# BT_module.net
KiCad netlist of a schematic drawn in EAGLE
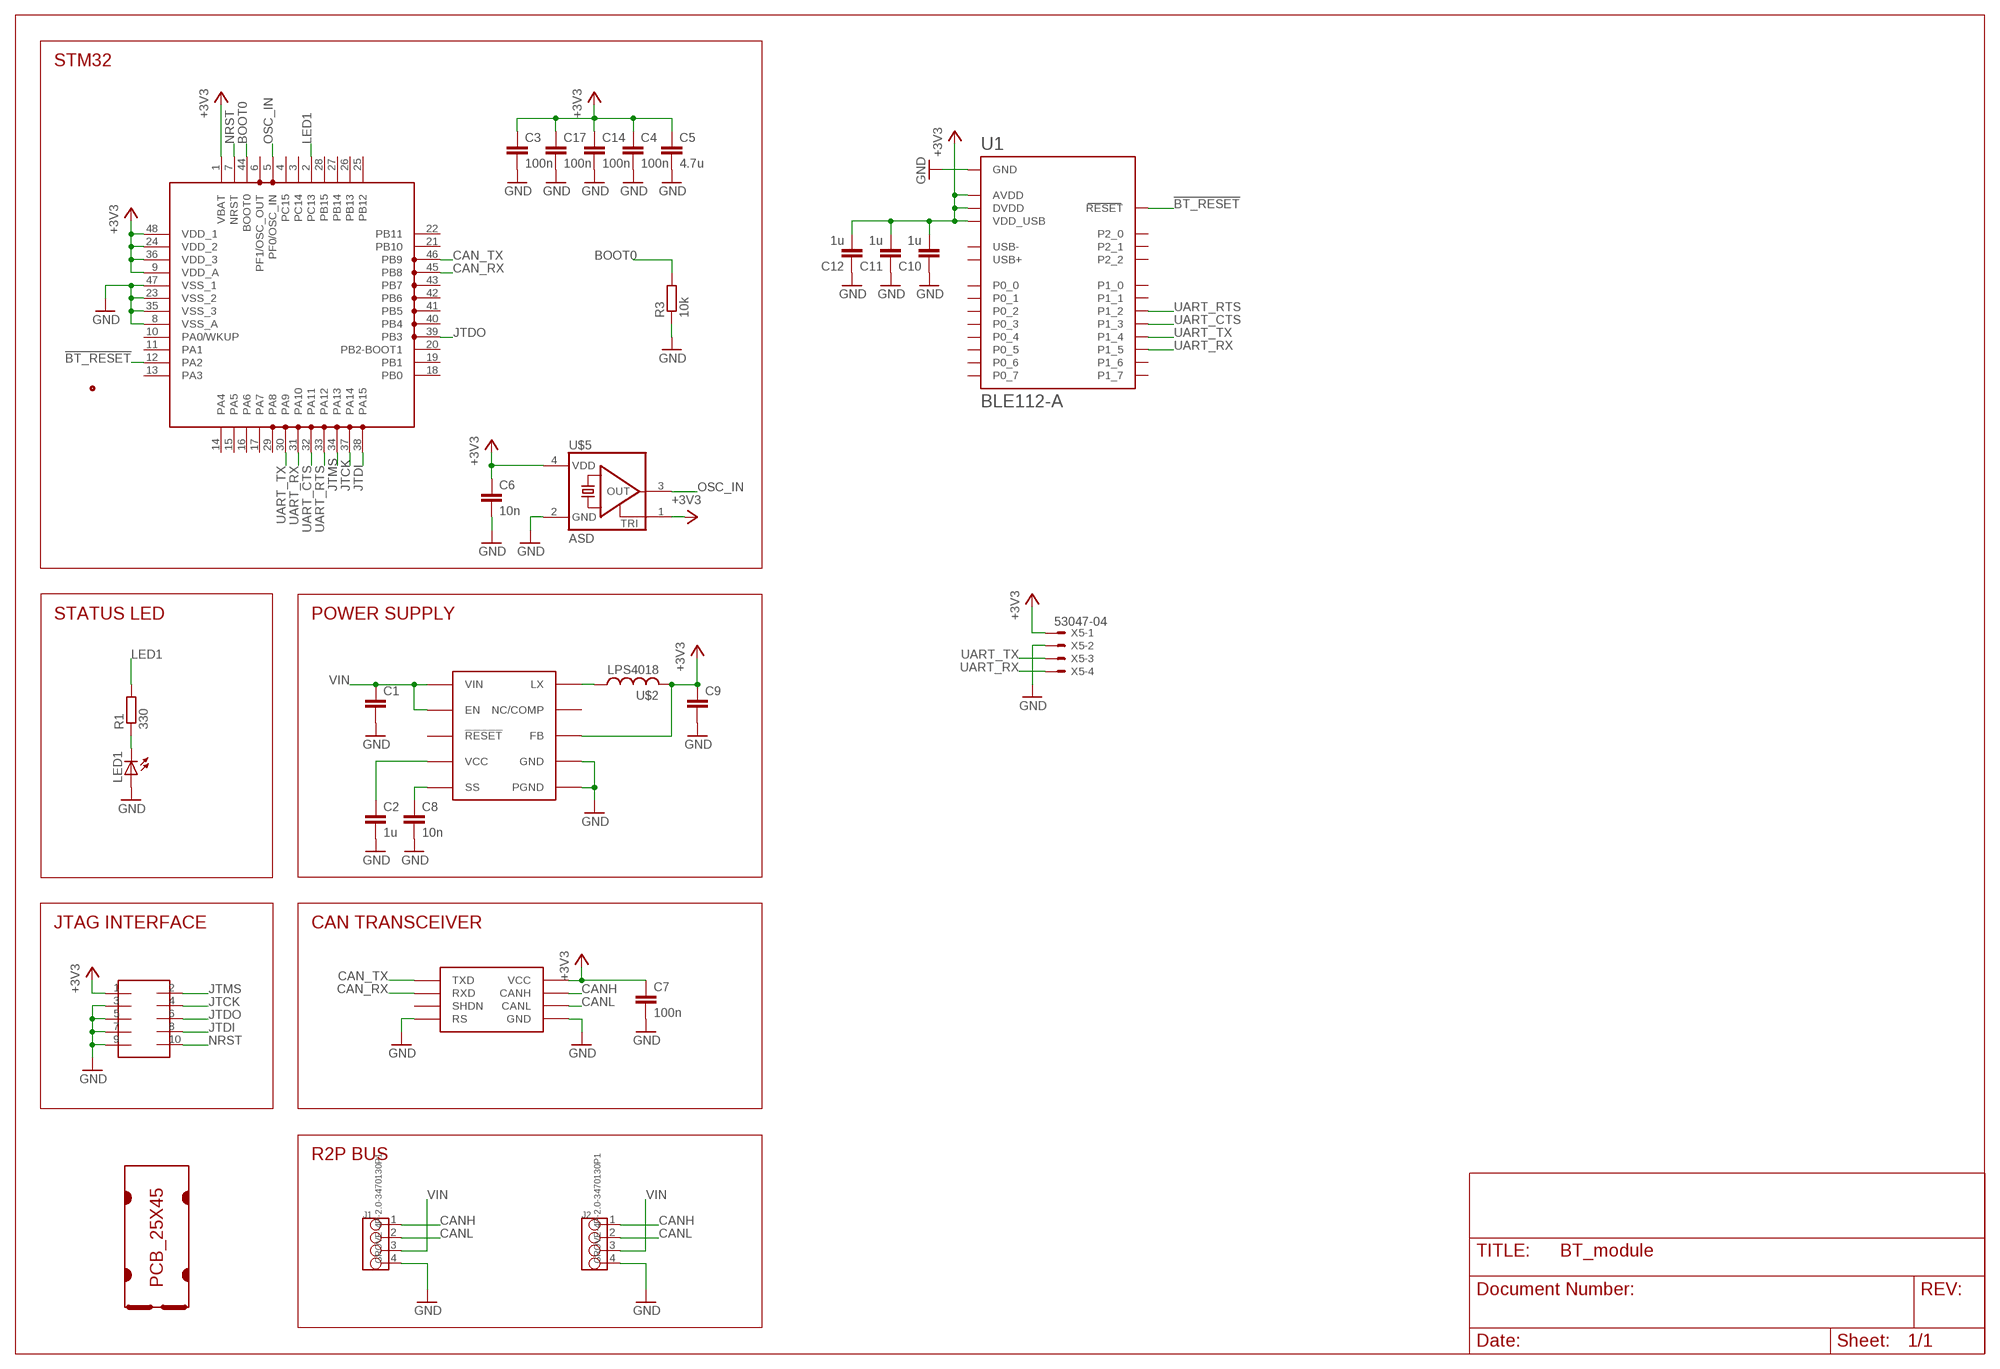
[diagram p0: schematic, sheet 1]

(export (version "E")
  (design (tool "Eeschema 10.0.6"))
  (components
    (comp (ref "C1")
      (value "C-EUC1206")
      (footprint "eagle-import:C1206")
      (libsource (lib "eagle-import") (part "C-EUC1206"))
    )
    (comp (ref "C2")
      (value "1u")
      (footprint "eagle-import:C0603")
      (libsource (lib "eagle-import") (part "C-EUC0603"))
    )
    (comp (ref "C3")
      (value "100n")
      (footprint "eagle-import:C0603")
      (libsource (lib "eagle-import") (part "C-EUC0603"))
    )
    (comp (ref "C4")
      (value "100n")
      (footprint "eagle-import:C0603")
      (libsource (lib "eagle-import") (part "C-EUC0603"))
    )
    (comp (ref "C5")
      (value "4.7u")
      (footprint "eagle-import:C0805")
      (libsource (lib "eagle-import") (part "C-EUC0805"))
    )
    (comp (ref "C6")
      (value "10n")
      (footprint "eagle-import:C0603")
      (libsource (lib "eagle-import") (part "C-EUC0603"))
    )
    (comp (ref "C7")
      (value "100n")
      (footprint "eagle-import:C0603")
      (libsource (lib "eagle-import") (part "C-EUC0603"))
    )
    (comp (ref "C8")
      (value "10n")
      (footprint "eagle-import:C0603")
      (libsource (lib "eagle-import") (part "C-EUC0603"))
    )
    (comp (ref "C9")
      (value "C-EUC0805")
      (footprint "eagle-import:C0805")
      (libsource (lib "eagle-import") (part "C-EUC0805"))
    )
    (comp (ref "C10")
      (value "1u")
      (footprint "eagle-import:C0603")
      (libsource (lib "eagle-import") (part "C-EUC0603"))
    )
    (comp (ref "C11")
      (value "1u")
      (footprint "eagle-import:C0603")
      (libsource (lib "eagle-import") (part "C-EUC0603"))
    )
    (comp (ref "C12")
      (value "1u")
      (footprint "eagle-import:C0603")
      (libsource (lib "eagle-import") (part "C-EUC0603"))
    )
    (comp (ref "C14")
      (value "100n")
      (footprint "eagle-import:C0603")
      (libsource (lib "eagle-import") (part "C-EUC0603"))
    )
    (comp (ref "C17")
      (value "100n")
      (footprint "eagle-import:C0603")
      (libsource (lib "eagle-import") (part "C-EUC0603"))
    )
    (comp (ref "J1")
      (value "GROVE-4P-2.0-3470130P1")
      (footprint "eagle-import:4P-2.0")
      (libsource (lib "eagle-import") (part "GROVE-4P-2.0-3470130P1"))
    )
    (comp (ref "J2")
      (value "GROVE-4P-2.0-3470130P1")
      (footprint "eagle-import:4P-2.0")
      (libsource (lib "eagle-import") (part "GROVE-4P-2.0-3470130P1"))
    )
    (comp (ref "LED1")
      (value "LEDCHIPLED_0805")
      (footprint "eagle-import:CHIPLED_0805")
      (libsource (lib "eagle-import") (part "LEDCHIPLED_0805"))
    )
    (comp (ref "R1")
      (value "330")
      (footprint "eagle-import:R0603")
      (libsource (lib "eagle-import") (part "R-EU_R0603"))
    )
    (comp (ref "R3")
      (value "10k")
      (footprint "eagle-import:R0603")
      (libsource (lib "eagle-import") (part "R-EU_R0603"))
    )
    (comp (ref "SOT1")
      (value "MAX3051EKA")
      (footprint "eagle-import:SOT23-8L")
      (libsource (lib "eagle-import") (part "MAX3051EKA"))
    )
    (comp (ref "U$1")
      (value "PCB_25X45")
      (footprint "eagle-import:25X45")
      (libsource (lib "eagle-import") (part "PCB_25X45"))
    )
    (comp (ref "U$2")
      (value "LPS4018")
      (footprint "eagle-import:LPS4018")
      (libsource (lib "eagle-import") (part "LPS4018"))
    )
    (comp (ref "U$3")
      (value "MAX17501")
      (footprint "eagle-import:TDFN-10")
      (libsource (lib "eagle-import") (part "MAX17501"))
    )
    (comp (ref "U$4")
      (value "FTSH-105TH")
      (footprint "eagle-import:FTSH-105-TH")
      (libsource (lib "eagle-import") (part "FTSH-105TH"))
    )
    (comp (ref "U$5")
      (value "ASD")
      (footprint "eagle-import:2.5X2")
      (libsource (lib "eagle-import") (part "ASD"))
    )
    (comp (ref "U$6")
      (value "STM32F303C")
      (footprint "eagle-import:LQFP48")
      (libsource (lib "eagle-import") (part "STM32F303C"))
    )
    (comp (ref "U1")
      (value "BLE112-A")
      (footprint "eagle-import:BLE112-A")
      (libsource (lib "eagle-import") (part "BLE112-A"))
    )
    (comp (ref "X5")
      (value "53047-04")
      (footprint "eagle-import:53047-04")
      (fields (field (name "MF") "WALDOM/MOLEX") (field (name "MPN") "53047-0410"))
      (libsource (lib "eagle-import") (part "53?-04047"))
    )
  )
  (nets
    (net (code "1") (name "+3V3") (class "Default")
      (node (ref "C10") (pin "2") (pinfunction "2_2") (pintype "passive"))
      (node (ref "C11") (pin "2") (pinfunction "2_2") (pintype "passive"))
      (node (ref "C12") (pin "2") (pinfunction "2_2") (pintype "passive"))
      (node (ref "C14") (pin "1") (pinfunction "1_1") (pintype "passive"))
      (node (ref "C17") (pin "1") (pinfunction "1_1") (pintype "passive"))
      (node (ref "C3") (pin "1") (pinfunction "1_1") (pintype "passive"))
      (node (ref "C4") (pin "1") (pinfunction "1_1") (pintype "passive"))
      (node (ref "C5") (pin "1") (pinfunction "1_1") (pintype "passive"))
      (node (ref "C6") (pin "1") (pinfunction "1_1") (pintype "passive"))
      (node (ref "C7") (pin "1") (pinfunction "1_1") (pintype "passive"))
      (node (ref "C9") (pin "1") (pinfunction "1_1") (pintype "passive"))
      (node (ref "SOT1") (pin "3") (pinfunction "VCC_3") (pintype "bidirectional"))
      (node (ref "U$2") (pin "P$2") (pinfunction "2_P$2") (pintype "passive"))
      (node (ref "U$3") (pin "P$5") (pinfunction "FB_P$5") (pintype "bidirectional"))
      (node (ref "U$4") (pin "1") (pinfunction "P$1_1") (pintype "bidirectional"))
      (node (ref "U$5") (pin "1") (pinfunction "TRI_1") (pintype "input"))
      (node (ref "U$5") (pin "4") (pinfunction "VDD_4") (pintype "power_in"))
      (node (ref "U$6") (pin "1") (pinfunction "VBAT_1") (pintype "bidirectional"))
      (node (ref "U$6") (pin "24") (pinfunction "VDD_2_24") (pintype "bidirectional"))
      (node (ref "U$6") (pin "36") (pinfunction "VDD_3_36") (pintype "bidirectional"))
      (node (ref "U$6") (pin "48") (pinfunction "VDD_1_48") (pintype "bidirectional"))
      (node (ref "U$6") (pin "9") (pinfunction "VDD_A_9") (pintype "bidirectional"))
      (node (ref "U1") (pin "AVDD") (pinfunction "AVDD_AVDD") (pintype "power_in"))
      (node (ref "U1") (pin "AVDD@2") (pinfunction "AVDD_AVDD@2") (pintype "power_in"))
      (node (ref "U1") (pin "DVDD") (pinfunction "DVDD_DVDD") (pintype "power_in"))
      (node (ref "U1") (pin "VDD_USB") (pinfunction "VDD_USB_VDD_USB") (pintype "power_in"))
      (node (ref "X5") (pin "1") (pinfunction "S_1") (pintype "passive"))
    )
    (net (code "2") (name "/BOOT0") (class "Default")
      (node (ref "R3") (pin "2") (pinfunction "2_2") (pintype "passive"))
      (node (ref "U$6") (pin "44") (pinfunction "BOOT0_44") (pintype "bidirectional"))
    )
    (net (code "3") (name "/CANH") (class "Default")
      (node (ref "J1") (pin "1") (pinfunction "1_1") (pintype "bidirectional"))
      (node (ref "J2") (pin "1") (pinfunction "1_1") (pintype "bidirectional"))
      (node (ref "SOT1") (pin "7") (pinfunction "CANH_7") (pintype "bidirectional"))
    )
    (net (code "4") (name "/CANL") (class "Default")
      (node (ref "J1") (pin "2") (pinfunction "2_2") (pintype "bidirectional"))
      (node (ref "J2") (pin "2") (pinfunction "2_2") (pintype "bidirectional"))
      (node (ref "SOT1") (pin "6") (pinfunction "CANL_6") (pintype "bidirectional"))
    )
    (net (code "5") (name "/CAN_RX") (class "Default")
      (node (ref "SOT1") (pin "4") (pinfunction "RXD_4") (pintype "bidirectional"))
      (node (ref "U$6") (pin "45") (pinfunction "PB8_45") (pintype "bidirectional"))
    )
    (net (code "6") (name "/CAN_TX") (class "Default")
      (node (ref "SOT1") (pin "1") (pinfunction "TXD_1") (pintype "bidirectional"))
      (node (ref "U$6") (pin "46") (pinfunction "PB9_46") (pintype "bidirectional"))
    )
    (net (code "7") (name "/JTCK") (class "Default")
      (node (ref "U$4") (pin "4") (pinfunction "P$4_4") (pintype "bidirectional"))
      (node (ref "U$6") (pin "37") (pinfunction "PA14_37") (pintype "bidirectional"))
    )
    (net (code "8") (name "/JTDI") (class "Default")
      (node (ref "U$4") (pin "8") (pinfunction "P$8_8") (pintype "bidirectional"))
      (node (ref "U$6") (pin "38") (pinfunction "PA15_38") (pintype "bidirectional"))
    )
    (net (code "9") (name "/JTDO") (class "Default")
      (node (ref "U$4") (pin "6") (pinfunction "P$6_6") (pintype "bidirectional"))
      (node (ref "U$6") (pin "39") (pinfunction "PB3_39") (pintype "bidirectional"))
    )
    (net (code "10") (name "/JTMS") (class "Default")
      (node (ref "U$4") (pin "2") (pinfunction "P$2_2") (pintype "bidirectional"))
      (node (ref "U$6") (pin "34") (pinfunction "PA13_34") (pintype "bidirectional"))
    )
    (net (code "11") (name "/LED1") (class "Default")
      (node (ref "R1") (pin "2") (pinfunction "2_2") (pintype "passive"))
      (node (ref "U$6") (pin "2") (pinfunction "PC13_2") (pintype "bidirectional"))
    )
    (net (code "12") (name "/NRST") (class "Default")
      (node (ref "U$4") (pin "10") (pinfunction "P$10_10") (pintype "bidirectional"))
      (node (ref "U$6") (pin "7") (pinfunction "NRST_7") (pintype "bidirectional"))
    )
    (net (code "13") (name "/OSC_IN") (class "Default")
      (node (ref "U$5") (pin "3") (pinfunction "OUT_3") (pintype "output"))
      (node (ref "U$6") (pin "5") (pinfunction "PF0/OSC_IN_5") (pintype "bidirectional"))
    )
    (net (code "14") (name "/UART_CTS") (class "Default")
      (node (ref "U$6") (pin "32") (pinfunction "PA11_32") (pintype "bidirectional"))
      (node (ref "U1") (pin "P1_3") (pinfunction "P1_3_P1_3") (pintype "bidirectional"))
    )
    (net (code "15") (name "/UART_RTS") (class "Default")
      (node (ref "U$6") (pin "33") (pinfunction "PA12_33") (pintype "bidirectional"))
      (node (ref "U1") (pin "P1_2") (pinfunction "P1_2_P1_2") (pintype "bidirectional"))
    )
    (net (code "16") (name "/UART_RX") (class "Default")
      (node (ref "U$6") (pin "31") (pinfunction "PA10_31") (pintype "bidirectional"))
      (node (ref "U1") (pin "P1_5") (pinfunction "P1_5_P1_5") (pintype "bidirectional"))
      (node (ref "X5") (pin "4") (pinfunction "S_4") (pintype "passive"))
    )
    (net (code "17") (name "/UART_TX") (class "Default")
      (node (ref "U$6") (pin "30") (pinfunction "PA9_30") (pintype "bidirectional"))
      (node (ref "U1") (pin "P1_4") (pinfunction "P1_4_P1_4") (pintype "bidirectional"))
      (node (ref "X5") (pin "3") (pinfunction "S_3") (pintype "passive"))
    )
    (net (code "18") (name "/VIN") (class "Default")
      (node (ref "C1") (pin "1") (pinfunction "1_1") (pintype "passive"))
      (node (ref "J1") (pin "3") (pinfunction "3_3") (pintype "bidirectional"))
      (node (ref "J2") (pin "3") (pinfunction "3_3") (pintype "bidirectional"))
      (node (ref "U$3") (pin "P$2") (pinfunction "VIN_P$2") (pintype "bidirectional"))
      (node (ref "U$3") (pin "P$3") (pinfunction "EN_P$3") (pintype "bidirectional"))
    )
    (net (code "19") (name "/~{BT_RESET}") (class "Default")
      (node (ref "U$6") (pin "12") (pinfunction "PA2_12") (pintype "bidirectional"))
      (node (ref "U1") (pin "RESET") (pinfunction "RESET_RESET") (pintype "input"))
    )
    (net (code "20") (name "GND") (class "Default")
      (node (ref "C1") (pin "2") (pinfunction "2_2") (pintype "passive"))
      (node (ref "C10") (pin "1") (pinfunction "1_1") (pintype "passive"))
      (node (ref "C11") (pin "1") (pinfunction "1_1") (pintype "passive"))
      (node (ref "C12") (pin "1") (pinfunction "1_1") (pintype "passive"))
      (node (ref "C14") (pin "2") (pinfunction "2_2") (pintype "passive"))
      (node (ref "C17") (pin "2") (pinfunction "2_2") (pintype "passive"))
      (node (ref "C2") (pin "2") (pinfunction "2_2") (pintype "passive"))
      (node (ref "C3") (pin "2") (pinfunction "2_2") (pintype "passive"))
      (node (ref "C4") (pin "2") (pinfunction "2_2") (pintype "passive"))
      (node (ref "C5") (pin "2") (pinfunction "2_2") (pintype "passive"))
      (node (ref "C6") (pin "2") (pinfunction "2_2") (pintype "passive"))
      (node (ref "C7") (pin "2") (pinfunction "2_2") (pintype "passive"))
      (node (ref "C8") (pin "2") (pinfunction "2_2") (pintype "passive"))
      (node (ref "C9") (pin "2") (pinfunction "2_2") (pintype "passive"))
      (node (ref "J1") (pin "4") (pinfunction "4_4") (pintype "bidirectional"))
      (node (ref "J2") (pin "4") (pinfunction "4_4") (pintype "bidirectional"))
      (node (ref "LED1") (pin "A") (pinfunction "A_A") (pintype "passive"))
      (node (ref "R3") (pin "1") (pinfunction "1_1") (pintype "passive"))
      (node (ref "SOT1") (pin "2") (pinfunction "GND_2") (pintype "bidirectional"))
      (node (ref "SOT1") (pin "8") (pinfunction "RS_8") (pintype "bidirectional"))
      (node (ref "U$3") (pin "P$1") (pinfunction "PGND_P$1") (pintype "bidirectional"))
      (node (ref "U$3") (pin "P$11") (pinfunction "PGND_P$11") (pintype "bidirectional"))
      (node (ref "U$3") (pin "P$9") (pinfunction "GND_P$9") (pintype "bidirectional"))
      (node (ref "U$4") (pin "3") (pinfunction "P$3_3") (pintype "bidirectional"))
      (node (ref "U$4") (pin "5") (pinfunction "P$5_5") (pintype "bidirectional"))
      (node (ref "U$4") (pin "7") (pinfunction "P$7_7") (pintype "bidirectional"))
      (node (ref "U$4") (pin "9") (pinfunction "P$9_9") (pintype "bidirectional"))
      (node (ref "U$5") (pin "2") (pinfunction "GND_2") (pintype "power_in"))
      (node (ref "U$6") (pin "23") (pinfunction "VSS_2_23") (pintype "bidirectional"))
      (node (ref "U$6") (pin "35") (pinfunction "VSS_3_35") (pintype "bidirectional"))
      (node (ref "U$6") (pin "47") (pinfunction "VSS_1_47") (pintype "bidirectional"))
      (node (ref "U$6") (pin "8") (pinfunction "VSS_A_8") (pintype "bidirectional"))
      (node (ref "U1") (pin "GND") (pinfunction "GND_GND") (pintype "power_in"))
      (node (ref "U1") (pin "GND@2") (pinfunction "GND_GND@2") (pintype "power_in"))
      (node (ref "U1") (pin "GND@3") (pinfunction "GND_GND@3") (pintype "power_in"))
      (node (ref "U1") (pin "GND@4") (pinfunction "GND_GND@4") (pintype "power_in"))
      (node (ref "X5") (pin "2") (pinfunction "S_2") (pintype "passive"))
    )
    (net (code "21") (name "Net-(LED1-PadC)") (class "Default")
      (node (ref "LED1") (pin "C") (pinfunction "C_C") (pintype "passive"))
      (node (ref "R1") (pin "1") (pinfunction "1_1") (pintype "passive"))
    )
    (net (code "22") (name "Net-(U$2-1)") (class "Default")
      (node (ref "U$2") (pin "P$1") (pinfunction "1_P$1") (pintype "passive"))
      (node (ref "U$3") (pin "P$10") (pinfunction "LX_P$10") (pintype "bidirectional"))
    )
    (net (code "23") (name "Net-(U$3-SS)") (class "Default")
      (node (ref "C8") (pin "1") (pinfunction "1_1") (pintype "passive"))
      (node (ref "U$3") (pin "P$6") (pinfunction "SS_P$6") (pintype "bidirectional"))
    )
    (net (code "24") (name "Net-(U$3-VCC)") (class "Default")
      (node (ref "C2") (pin "1") (pinfunction "1_1") (pintype "passive"))
      (node (ref "U$3") (pin "P$4") (pinfunction "VCC_P$4") (pintype "bidirectional"))
    )
    (net (code "25") (name "unconnected-(SOT1-SHDN-Pad5)") (class "Default")
      (node (ref "SOT1") (pin "5") (pinfunction "SHDN_5") (pintype "bidirectional"))
    )
    (net (code "26") (name "unconnected-(U$3-NC{slash}COMP-PadP$7)") (class "Default")
      (node (ref "U$3") (pin "P$7") (pinfunction "NC/COMP_P$7") (pintype "bidirectional"))
    )
    (net (code "27") (name "unconnected-(U$3-~{RESET}-PadP$8)") (class "Default")
      (node (ref "U$3") (pin "P$8") (pinfunction "~{RESET}_P$8") (pintype "bidirectional"))
    )
    (net (code "28") (name "unconnected-(U$6-PA0{slash}WKUP-Pad10)") (class "Default")
      (node (ref "U$6") (pin "10") (pinfunction "PA0/WKUP_10") (pintype "bidirectional"))
    )
    (net (code "29") (name "unconnected-(U$6-PA1-Pad11)") (class "Default")
      (node (ref "U$6") (pin "11") (pinfunction "PA1_11") (pintype "bidirectional"))
    )
    (net (code "30") (name "unconnected-(U$6-PA3-Pad13)") (class "Default")
      (node (ref "U$6") (pin "13") (pinfunction "PA3_13") (pintype "bidirectional"))
    )
    (net (code "31") (name "unconnected-(U$6-PA4-Pad14)") (class "Default")
      (node (ref "U$6") (pin "14") (pinfunction "PA4_14") (pintype "bidirectional"))
    )
    (net (code "32") (name "unconnected-(U$6-PA5-Pad15)") (class "Default")
      (node (ref "U$6") (pin "15") (pinfunction "PA5_15") (pintype "bidirectional"))
    )
    (net (code "33") (name "unconnected-(U$6-PA6-Pad16)") (class "Default")
      (node (ref "U$6") (pin "16") (pinfunction "PA6_16") (pintype "bidirectional"))
    )
    (net (code "34") (name "unconnected-(U$6-PA7-Pad17)") (class "Default")
      (node (ref "U$6") (pin "17") (pinfunction "PA7_17") (pintype "bidirectional"))
    )
    (net (code "35") (name "unconnected-(U$6-PA8-Pad29)") (class "Default")
      (node (ref "U$6") (pin "29") (pinfunction "PA8_29") (pintype "bidirectional"))
    )
    (net (code "36") (name "unconnected-(U$6-PB0-Pad18)") (class "Default")
      (node (ref "U$6") (pin "18") (pinfunction "PB0_18") (pintype "bidirectional"))
    )
    (net (code "37") (name "unconnected-(U$6-PB1-Pad19)") (class "Default")
      (node (ref "U$6") (pin "19") (pinfunction "PB1_19") (pintype "bidirectional"))
    )
    (net (code "38") (name "unconnected-(U$6-PB2-BOOT1-Pad20)") (class "Default")
      (node (ref "U$6") (pin "20") (pinfunction "PB2-BOOT1_20") (pintype "bidirectional"))
    )
    (net (code "39") (name "unconnected-(U$6-PB4-Pad40)") (class "Default")
      (node (ref "U$6") (pin "40") (pinfunction "PB4_40") (pintype "bidirectional"))
    )
    (net (code "40") (name "unconnected-(U$6-PB5-Pad41)") (class "Default")
      (node (ref "U$6") (pin "41") (pinfunction "PB5_41") (pintype "bidirectional"))
    )
    (net (code "41") (name "unconnected-(U$6-PB6-Pad42)") (class "Default")
      (node (ref "U$6") (pin "42") (pinfunction "PB6_42") (pintype "bidirectional"))
    )
    (net (code "42") (name "unconnected-(U$6-PB7-Pad43)") (class "Default")
      (node (ref "U$6") (pin "43") (pinfunction "PB7_43") (pintype "bidirectional"))
    )
    (net (code "43") (name "unconnected-(U$6-PB10-Pad21)") (class "Default")
      (node (ref "U$6") (pin "21") (pinfunction "PB10_21") (pintype "bidirectional"))
    )
    (net (code "44") (name "unconnected-(U$6-PB11-Pad22)") (class "Default")
      (node (ref "U$6") (pin "22") (pinfunction "PB11_22") (pintype "bidirectional"))
    )
    (net (code "45") (name "unconnected-(U$6-PB12-Pad25)") (class "Default")
      (node (ref "U$6") (pin "25") (pinfunction "PB12_25") (pintype "bidirectional"))
    )
    (net (code "46") (name "unconnected-(U$6-PB13-Pad26)") (class "Default")
      (node (ref "U$6") (pin "26") (pinfunction "PB13_26") (pintype "bidirectional"))
    )
    (net (code "47") (name "unconnected-(U$6-PB14-Pad27)") (class "Default")
      (node (ref "U$6") (pin "27") (pinfunction "PB14_27") (pintype "bidirectional"))
    )
    (net (code "48") (name "unconnected-(U$6-PB15-Pad28)") (class "Default")
      (node (ref "U$6") (pin "28") (pinfunction "PB15_28") (pintype "bidirectional"))
    )
    (net (code "49") (name "unconnected-(U$6-PC14-Pad3)") (class "Default")
      (node (ref "U$6") (pin "3") (pinfunction "PC14_3") (pintype "bidirectional"))
    )
    (net (code "50") (name "unconnected-(U$6-PC15-Pad4)") (class "Default")
      (node (ref "U$6") (pin "4") (pinfunction "PC15_4") (pintype "bidirectional"))
    )
    (net (code "51") (name "unconnected-(U$6-PF1{slash}OSC_OUT-Pad6)") (class "Default")
      (node (ref "U$6") (pin "6") (pinfunction "PF1/OSC_OUT_6") (pintype "bidirectional"))
    )
    (net (code "52") (name "unconnected-(U1-PadP0_0)") (class "Default")
      (node (ref "U1") (pin "P0_0") (pinfunction "P0_0_P0_0") (pintype "bidirectional"))
    )
    (net (code "53") (name "unconnected-(U1-PadP0_1)") (class "Default")
      (node (ref "U1") (pin "P0_1") (pinfunction "P0_1_P0_1") (pintype "bidirectional"))
    )
    (net (code "54") (name "unconnected-(U1-PadP0_2)") (class "Default")
      (node (ref "U1") (pin "P0_2") (pinfunction "P0_2_P0_2") (pintype "bidirectional"))
    )
    (net (code "55") (name "unconnected-(U1-PadP0_3)") (class "Default")
      (node (ref "U1") (pin "P0_3") (pinfunction "P0_3_P0_3") (pintype "bidirectional"))
    )
    (net (code "56") (name "unconnected-(U1-PadP0_4)") (class "Default")
      (node (ref "U1") (pin "P0_4") (pinfunction "P0_4_P0_4") (pintype "bidirectional"))
    )
    (net (code "57") (name "unconnected-(U1-PadP0_5)") (class "Default")
      (node (ref "U1") (pin "P0_5") (pinfunction "P0_5_P0_5") (pintype "bidirectional"))
    )
    (net (code "58") (name "unconnected-(U1-PadP0_6)") (class "Default")
      (node (ref "U1") (pin "P0_6") (pinfunction "P0_6_P0_6") (pintype "bidirectional"))
    )
    (net (code "59") (name "unconnected-(U1-PadP0_7)") (class "Default")
      (node (ref "U1") (pin "P0_7") (pinfunction "P0_7_P0_7") (pintype "bidirectional"))
    )
    (net (code "60") (name "unconnected-(U1-PadP1_0)") (class "Default")
      (node (ref "U1") (pin "P1_0") (pinfunction "P1_0_P1_0") (pintype "bidirectional"))
    )
    (net (code "61") (name "unconnected-(U1-PadP1_1)") (class "Default")
      (node (ref "U1") (pin "P1_1") (pinfunction "P1_1_P1_1") (pintype "bidirectional"))
    )
    (net (code "62") (name "unconnected-(U1-PadP1_6)") (class "Default")
      (node (ref "U1") (pin "P1_6") (pinfunction "P1_6_P1_6") (pintype "bidirectional"))
    )
    (net (code "63") (name "unconnected-(U1-PadP1_7)") (class "Default")
      (node (ref "U1") (pin "P1_7") (pinfunction "P1_7_P1_7") (pintype "bidirectional"))
    )
    (net (code "64") (name "unconnected-(U1-PadP2_0)") (class "Default")
      (node (ref "U1") (pin "P2_0") (pinfunction "P2_0_P2_0") (pintype "bidirectional"))
    )
    (net (code "65") (name "unconnected-(U1-PadP2_1)") (class "Default")
      (node (ref "U1") (pin "P2_1") (pinfunction "P2_1_P2_1") (pintype "bidirectional"))
    )
    (net (code "66") (name "unconnected-(U1-PadP2_2)") (class "Default")
      (node (ref "U1") (pin "P2_2") (pinfunction "P2_2_P2_2") (pintype "bidirectional"))
    )
    (net (code "67") (name "unconnected-(U1-PadUSB+)") (class "Default")
      (node (ref "U1") (pin "USB+") (pinfunction "USB+_USB+") (pintype "bidirectional"))
    )
    (net (code "68") (name "unconnected-(U1-PadUSB-)") (class "Default")
      (node (ref "U1") (pin "USB-") (pinfunction "USB-_USB-") (pintype "bidirectional"))
    )
  )
)
